# controller_v0.net
KiCad netlist of a schematic drawn in EAGLE
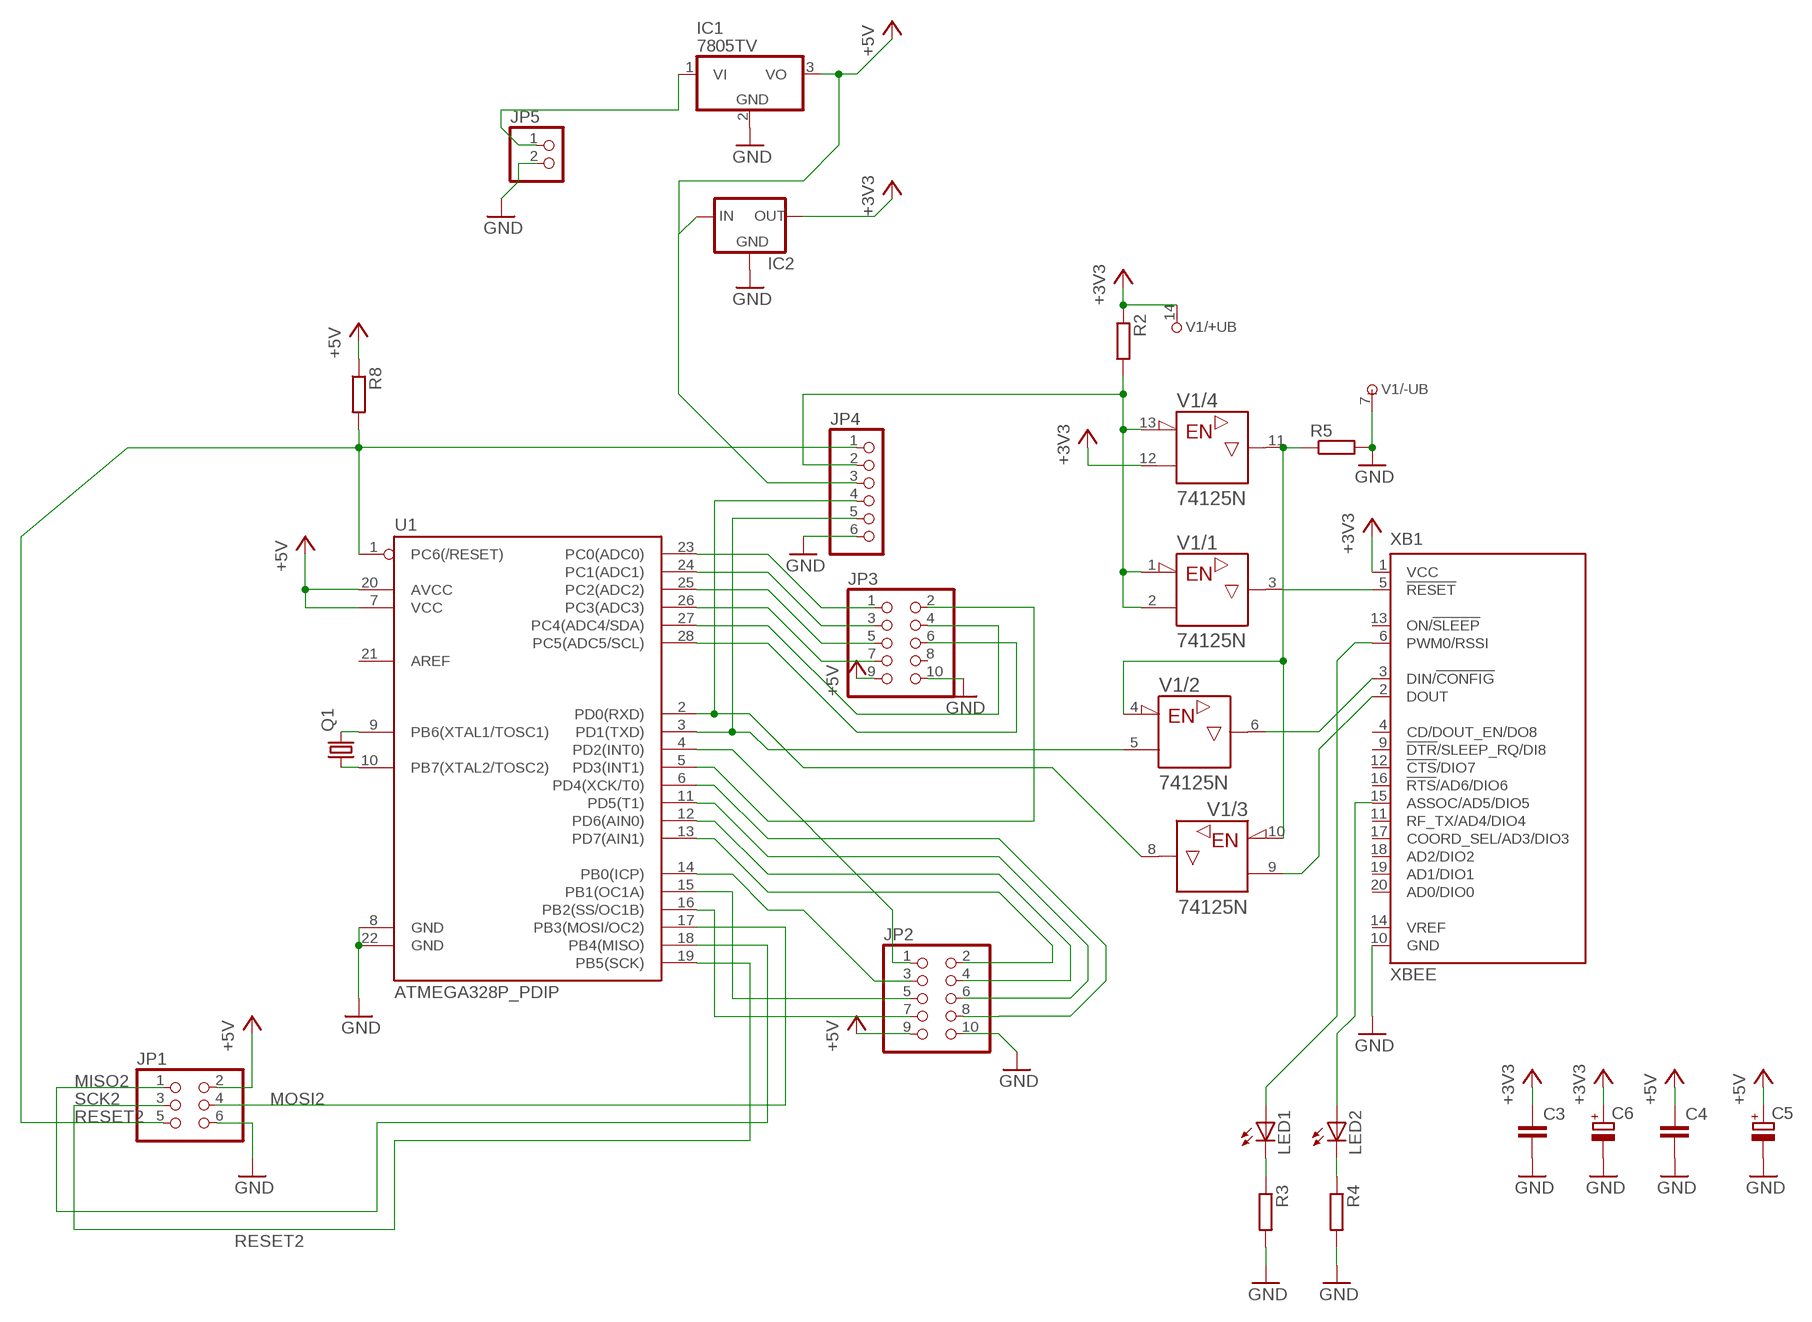
[diagram p0: schematic, sheet 1]

(export (version "E")
  (design (tool "Eeschema 10.0.6"))
  (components
    (comp (ref "C3")
      (value "C-EU025-025X050")
      (footprint "eagle-import:C025-025X050")
      (libsource (lib "eagle-import") (part "C-EU025-025X050"))
    )
    (comp (ref "C4")
      (value "C-EU025-025X050")
      (footprint "eagle-import:C025-025X050")
      (libsource (lib "eagle-import") (part "C-EU025-025X050"))
    )
    (comp (ref "C5")
      (value "CPOL-EUE2.5-6")
      (footprint "eagle-import:E2,5-6")
      (libsource (lib "eagle-import") (part "CPOL-EUE2.5-6"))
    )
    (comp (ref "C6")
      (value "CPOL-EUE2.5-6")
      (footprint "eagle-import:E2,5-6")
      (libsource (lib "eagle-import") (part "CPOL-EUE2.5-6"))
    )
    (comp (ref "IC1")
      (value "7805TV")
      (footprint "eagle-import:TO220V")
      (libsource (lib "eagle-import") (part "78TV05"))
    )
    (comp (ref "IC2")
      (value "78LXX")
      (footprint "eagle-import:78LXX")
      (libsource (lib "eagle-import") (part "78LXX"))
    )
    (comp (ref "JP1")
      (value "PINHD-2X3")
      (footprint "eagle-import:2X03")
      (libsource (lib "eagle-import") (part "PINHD-2X3"))
    )
    (comp (ref "JP2")
      (value "PINHD-2X5")
      (footprint "eagle-import:2X05")
      (libsource (lib "eagle-import") (part "PINHD-2X5"))
    )
    (comp (ref "JP3")
      (value "PINHD-2X5")
      (footprint "eagle-import:2X05")
      (libsource (lib "eagle-import") (part "PINHD-2X5"))
    )
    (comp (ref "JP4")
      (value "PINHD-1X6")
      (footprint "eagle-import:1X06")
      (libsource (lib "eagle-import") (part "PINHD-1X6"))
    )
    (comp (ref "JP5")
      (value "PINHD-1X2")
      (footprint "eagle-import:1X02")
      (libsource (lib "eagle-import") (part "PINHD-1X2"))
    )
    (comp (ref "LED1")
      (value "LED3MM")
      (footprint "eagle-import:LED3MM")
      (libsource (lib "eagle-import") (part "LED3MM"))
    )
    (comp (ref "LED2")
      (value "LED3MM")
      (footprint "eagle-import:LED3MM")
      (libsource (lib "eagle-import") (part "LED3MM"))
    )
    (comp (ref "Q1")
      (value "CRYSTALHC49S")
      (footprint "eagle-import:HC49_S")
      (libsource (lib "eagle-import") (part "CRYSTALHC49S"))
    )
    (comp (ref "R2")
      (value "R-EU_0204/7")
      (footprint "eagle-import:0204_7")
      (libsource (lib "eagle-import") (part "R-EU_0204/7"))
    )
    (comp (ref "R3")
      (value "R-EU_0204/7")
      (footprint "eagle-import:0204_7")
      (libsource (lib "eagle-import") (part "R-EU_0204/7"))
    )
    (comp (ref "R4")
      (value "R-EU_0204/7")
      (footprint "eagle-import:0204_7")
      (libsource (lib "eagle-import") (part "R-EU_0204/7"))
    )
    (comp (ref "R5")
      (value "R-EU_0204/7")
      (footprint "eagle-import:0204_7")
      (libsource (lib "eagle-import") (part "R-EU_0204/7"))
    )
    (comp (ref "R8")
      (value "R-EU_0204/7")
      (footprint "eagle-import:0204_7")
      (libsource (lib "eagle-import") (part "R-EU_0204/7"))
    )
    (comp (ref "U1")
      (value "ATMEGA328P_PDIP")
      (footprint "eagle-import:DIL28-3")
      (libsource (lib "eagle-import") (part "ATMEGA328P_PDIP"))
    )
    (comp (ref "V1")
      (value "74125N")
      (footprint "eagle-import:DIL14")
      (libsource (lib "eagle-import") (part "74125N"))
    )
    (comp (ref "XB1")
      (value "XBEE")
      (footprint "eagle-import:XBEE")
      (fields (field (name "MPN") "XBP24-Z7UIT-004"))
      (libsource (lib "eagle-import") (part "XBEE"))
    )
  )
  (nets
    (net (code "1") (name "+3V3") (class "Default")
      (node (ref "C3") (pin "1") (pinfunction "1_1") (pintype "passive"))
      (node (ref "C6") (pin "+") (pinfunction "+_+") (pintype "passive"))
      (node (ref "IC2") (pin "OUT") (pinfunction "OUT_OUT") (pintype "passive"))
      (node (ref "R2") (pin "1") (pinfunction "1_1") (pintype "passive"))
      (node (ref "V1") (pin "12") (pinfunction "A_12") (pintype "input"))
      (node (ref "V1") (pin "14") (pinfunction "+UB_14") (pintype "power_in"))
      (node (ref "XB1") (pin "1") (pinfunction "VCC_1") (pintype "power_in"))
    )
    (net (code "2") (name "+5V") (class "Default")
      (node (ref "C4") (pin "1") (pinfunction "1_1") (pintype "passive"))
      (node (ref "C5") (pin "+") (pinfunction "+_+") (pintype "passive"))
      (node (ref "IC1") (pin "3") (pinfunction "VO_3") (pintype "passive"))
      (node (ref "IC2") (pin "IN") (pinfunction "IN_IN") (pintype "input"))
      (node (ref "JP1") (pin "2") (pinfunction "2_2") (pintype "passive"))
      (node (ref "JP2") (pin "9") (pinfunction "9_9") (pintype "passive"))
      (node (ref "JP3") (pin "9") (pinfunction "9_9") (pintype "passive"))
      (node (ref "JP4") (pin "3") (pinfunction "3_3") (pintype "passive"))
      (node (ref "R8") (pin "1") (pinfunction "1_1") (pintype "passive"))
      (node (ref "U1") (pin "20") (pinfunction "AVCC_20") (pintype "bidirectional"))
      (node (ref "U1") (pin "7") (pinfunction "VCC_7") (pintype "bidirectional"))
    )
    (net (code "3") (name "/MISO2") (class "Default")
      (node (ref "JP1") (pin "1") (pinfunction "1_1") (pintype "passive"))
      (node (ref "U1") (pin "18") (pinfunction "PB4(MISO)_18") (pintype "bidirectional"))
    )
    (net (code "4") (name "/MOSI2") (class "Default")
      (node (ref "JP1") (pin "4") (pinfunction "4_4") (pintype "passive"))
      (node (ref "U1") (pin "17") (pinfunction "PB3(MOSI/OC2)_17") (pintype "bidirectional"))
    )
    (net (code "5") (name "/RESET2") (class "Default")
      (node (ref "JP1") (pin "5") (pinfunction "5_5") (pintype "passive"))
      (node (ref "JP4") (pin "1") (pinfunction "1_1") (pintype "passive"))
      (node (ref "R8") (pin "2") (pinfunction "2_2") (pintype "passive"))
      (node (ref "U1") (pin "1") (pinfunction "PC6(/RESET)_1") (pintype "bidirectional"))
    )
    (net (code "6") (name "/SCK2") (class "Default")
      (node (ref "JP1") (pin "3") (pinfunction "3_3") (pintype "passive"))
      (node (ref "U1") (pin "19") (pinfunction "PB5(SCK)_19") (pintype "bidirectional"))
    )
    (net (code "7") (name "GND") (class "Default")
      (node (ref "C3") (pin "2") (pinfunction "2_2") (pintype "passive"))
      (node (ref "C4") (pin "2") (pinfunction "2_2") (pintype "passive"))
      (node (ref "C5") (pin "-") (pinfunction "-_-") (pintype "passive"))
      (node (ref "C6") (pin "-") (pinfunction "-_-") (pintype "passive"))
      (node (ref "IC1") (pin "2") (pinfunction "GND_2") (pintype "passive"))
      (node (ref "IC2") (pin "GND") (pinfunction "GND_GND") (pintype "input"))
      (node (ref "JP1") (pin "6") (pinfunction "6_6") (pintype "passive"))
      (node (ref "JP2") (pin "10") (pinfunction "10_10") (pintype "passive"))
      (node (ref "JP3") (pin "10") (pinfunction "10_10") (pintype "passive"))
      (node (ref "JP4") (pin "6") (pinfunction "6_6") (pintype "passive"))
      (node (ref "JP5") (pin "2") (pinfunction "2_2") (pintype "passive"))
      (node (ref "R3") (pin "2") (pinfunction "2_2") (pintype "passive"))
      (node (ref "R4") (pin "2") (pinfunction "2_2") (pintype "passive"))
      (node (ref "R5") (pin "2") (pinfunction "2_2") (pintype "passive"))
      (node (ref "U1") (pin "22") (pinfunction "GND_22") (pintype "bidirectional"))
      (node (ref "U1") (pin "8") (pinfunction "GND_8") (pintype "bidirectional"))
      (node (ref "V1") (pin "7") (pinfunction "-UB_7") (pintype "power_in"))
      (node (ref "XB1") (pin "10") (pinfunction "GND_10") (pintype "power_in"))
    )
    (net (code "8") (name "Net-(IC1-VI)") (class "Default")
      (node (ref "IC1") (pin "1") (pinfunction "VI_1") (pintype "input"))
      (node (ref "JP5") (pin "1") (pinfunction "1_1") (pintype "passive"))
    )
    (net (code "9") (name "Net-(LED1-C)") (class "Default")
      (node (ref "LED1") (pin "K") (pinfunction "C_K") (pintype "passive"))
      (node (ref "R3") (pin "1") (pinfunction "1_1") (pintype "passive"))
    )
    (net (code "10") (name "Net-(LED2-C)") (class "Default")
      (node (ref "LED2") (pin "K") (pinfunction "C_K") (pintype "passive"))
      (node (ref "R4") (pin "1") (pinfunction "1_1") (pintype "passive"))
    )
    (net (code "11") (name "Net-(U1-PB0(ICP))") (class "Default")
      (node (ref "JP2") (pin "3") (pinfunction "3_3") (pintype "passive"))
      (node (ref "U1") (pin "14") (pinfunction "PB0(ICP)_14") (pintype "bidirectional"))
    )
    (net (code "12") (name "Net-(U1-PB1(OC1A))") (class "Default")
      (node (ref "JP2") (pin "5") (pinfunction "5_5") (pintype "passive"))
      (node (ref "U1") (pin "15") (pinfunction "PB1(OC1A)_15") (pintype "bidirectional"))
    )
    (net (code "13") (name "Net-(U1-PB2(SS{slash}OC1B))") (class "Default")
      (node (ref "JP2") (pin "7") (pinfunction "7_7") (pintype "passive"))
      (node (ref "U1") (pin "16") (pinfunction "PB2(SS/OC1B)_16") (pintype "bidirectional"))
    )
    (net (code "14") (name "Net-(U1-PB6(XTAL1{slash}TOSC1))") (class "Default")
      (node (ref "Q1") (pin "2") (pinfunction "2_2") (pintype "passive"))
      (node (ref "U1") (pin "9") (pinfunction "PB6(XTAL1/TOSC1)_9") (pintype "bidirectional"))
    )
    (net (code "15") (name "Net-(U1-PB7(XTAL2{slash}TOSC2))") (class "Default")
      (node (ref "Q1") (pin "1") (pinfunction "1_1") (pintype "passive"))
      (node (ref "U1") (pin "10") (pinfunction "PB7(XTAL2/TOSC2)_10") (pintype "bidirectional"))
    )
    (net (code "16") (name "Net-(U1-PC0(ADC0))") (class "Default")
      (node (ref "JP3") (pin "1") (pinfunction "1_1") (pintype "passive"))
      (node (ref "U1") (pin "23") (pinfunction "PC0(ADC0)_23") (pintype "bidirectional"))
    )
    (net (code "17") (name "Net-(U1-PC1(ADC1))") (class "Default")
      (node (ref "JP3") (pin "3") (pinfunction "3_3") (pintype "passive"))
      (node (ref "U1") (pin "24") (pinfunction "PC1(ADC1)_24") (pintype "bidirectional"))
    )
    (net (code "18") (name "Net-(U1-PC2(ADC2))") (class "Default")
      (node (ref "JP3") (pin "5") (pinfunction "5_5") (pintype "passive"))
      (node (ref "U1") (pin "25") (pinfunction "PC2(ADC2)_25") (pintype "bidirectional"))
    )
    (net (code "19") (name "Net-(U1-PC3(ADC3))") (class "Default")
      (node (ref "JP3") (pin "7") (pinfunction "7_7") (pintype "passive"))
      (node (ref "U1") (pin "26") (pinfunction "PC3(ADC3)_26") (pintype "bidirectional"))
    )
    (net (code "20") (name "Net-(U1-PC4(ADC4{slash}SDA))") (class "Default")
      (node (ref "JP3") (pin "4") (pinfunction "4_4") (pintype "passive"))
      (node (ref "U1") (pin "27") (pinfunction "PC4(ADC4/SDA)_27") (pintype "bidirectional"))
    )
    (net (code "21") (name "Net-(U1-PC5(ADC5{slash}SCL))") (class "Default")
      (node (ref "JP3") (pin "6") (pinfunction "6_6") (pintype "passive"))
      (node (ref "U1") (pin "28") (pinfunction "PC5(ADC5/SCL)_28") (pintype "bidirectional"))
    )
    (net (code "22") (name "Net-(U1-PD0(RXD))") (class "Default")
      (node (ref "JP4") (pin "4") (pinfunction "4_4") (pintype "passive"))
      (node (ref "U1") (pin "2") (pinfunction "PD0(RXD)_2") (pintype "bidirectional"))
      (node (ref "V1") (pin "8") (pinfunction "Y_8") (pintype "tri_state"))
    )
    (net (code "23") (name "Net-(U1-PD1(TXD))") (class "Default")
      (node (ref "JP4") (pin "5") (pinfunction "5_5") (pintype "passive"))
      (node (ref "U1") (pin "3") (pinfunction "PD1(TXD)_3") (pintype "bidirectional"))
      (node (ref "V1") (pin "5") (pinfunction "A_5") (pintype "input"))
    )
    (net (code "24") (name "Net-(U1-PD2(INT0))") (class "Default")
      (node (ref "JP2") (pin "1") (pinfunction "1_1") (pintype "passive"))
      (node (ref "U1") (pin "4") (pinfunction "PD2(INT0)_4") (pintype "bidirectional"))
    )
    (net (code "25") (name "Net-(U1-PD3(INT1))") (class "Default")
      (node (ref "JP3") (pin "2") (pinfunction "2_2") (pintype "passive"))
      (node (ref "U1") (pin "5") (pinfunction "PD3(INT1)_5") (pintype "bidirectional"))
    )
    (net (code "26") (name "Net-(U1-PD4(XCK{slash}T0))") (class "Default")
      (node (ref "JP2") (pin "8") (pinfunction "8_8") (pintype "passive"))
      (node (ref "U1") (pin "6") (pinfunction "PD4(XCK/T0)_6") (pintype "bidirectional"))
    )
    (net (code "27") (name "Net-(U1-PD5(T1))") (class "Default")
      (node (ref "JP2") (pin "6") (pinfunction "6_6") (pintype "passive"))
      (node (ref "U1") (pin "11") (pinfunction "PD5(T1)_11") (pintype "bidirectional"))
    )
    (net (code "28") (name "Net-(U1-PD6(AIN0))") (class "Default")
      (node (ref "JP2") (pin "4") (pinfunction "4_4") (pintype "passive"))
      (node (ref "U1") (pin "12") (pinfunction "PD6(AIN0)_12") (pintype "bidirectional"))
    )
    (net (code "29") (name "Net-(U1-PD7(AIN1))") (class "Default")
      (node (ref "JP2") (pin "2") (pinfunction "2_2") (pintype "passive"))
      (node (ref "U1") (pin "13") (pinfunction "PD7(AIN1)_13") (pintype "bidirectional"))
    )
    (net (code "30") (name "Net-(V1C-A)") (class "Default")
      (node (ref "JP4") (pin "2") (pinfunction "2_2") (pintype "passive"))
      (node (ref "R2") (pin "2") (pinfunction "2_2") (pintype "passive"))
      (node (ref "V1") (pin "1") (pinfunction "~{G}_1") (pintype "input"))
      (node (ref "V1") (pin "13") (pinfunction "~{G}_13") (pintype "input"))
      (node (ref "V1") (pin "2") (pinfunction "A_2") (pintype "input"))
    )
    (net (code "31") (name "Net-(V1C-Y)") (class "Default")
      (node (ref "V1") (pin "3") (pinfunction "Y_3") (pintype "tri_state"))
      (node (ref "XB1") (pin "5") (pinfunction "~{RESET}_5") (pintype "input"))
    )
    (net (code "32") (name "Net-(V1D-Y)") (class "Default")
      (node (ref "V1") (pin "6") (pinfunction "Y_6") (pintype "tri_state"))
      (node (ref "XB1") (pin "3") (pinfunction "DIN/~{CONFIG}_3") (pintype "input"))
    )
    (net (code "33") (name "Net-(V1D-~{G})") (class "Default")
      (node (ref "R5") (pin "1") (pinfunction "1_1") (pintype "passive"))
      (node (ref "V1") (pin "10") (pinfunction "~{G}_10") (pintype "input"))
      (node (ref "V1") (pin "11") (pinfunction "Y_11") (pintype "tri_state"))
      (node (ref "V1") (pin "4") (pinfunction "~{G}_4") (pintype "input"))
    )
    (net (code "34") (name "Net-(V1E-A)") (class "Default")
      (node (ref "V1") (pin "9") (pinfunction "A_9") (pintype "input"))
      (node (ref "XB1") (pin "2") (pinfunction "DOUT_2") (pintype "output"))
    )
    (net (code "35") (name "Net-(XB1-ASSOC{slash}AD5{slash}DIO5)") (class "Default")
      (node (ref "LED2") (pin "A") (pinfunction "A_A") (pintype "passive"))
      (node (ref "XB1") (pin "15") (pinfunction "ASSOC/AD5/DIO5_15") (pintype "bidirectional"))
    )
    (net (code "36") (name "Net-(XB1-PWM0{slash}RSSI)") (class "Default")
      (node (ref "LED1") (pin "A") (pinfunction "A_A") (pintype "passive"))
      (node (ref "XB1") (pin "6") (pinfunction "PWM0/RSSI_6") (pintype "output"))
    )
    (net (code "37") (name "unconnected-(JP3-Pad8)") (class "Default")
      (node (ref "JP3") (pin "8") (pinfunction "8_8") (pintype "passive"))
    )
    (net (code "38") (name "unconnected-(U1-AREF-Pad21)") (class "Default")
      (node (ref "U1") (pin "21") (pinfunction "AREF_21") (pintype "bidirectional"))
    )
    (net (code "39") (name "unconnected-(XB1-AD0{slash}DIO0-Pad20)") (class "Default")
      (node (ref "XB1") (pin "20") (pinfunction "AD0/DIO0_20") (pintype "bidirectional"))
    )
    (net (code "40") (name "unconnected-(XB1-AD1{slash}DIO1-Pad19)") (class "Default")
      (node (ref "XB1") (pin "19") (pinfunction "AD1/DIO1_19") (pintype "bidirectional"))
    )
    (net (code "41") (name "unconnected-(XB1-AD2{slash}DIO2-Pad18)") (class "Default")
      (node (ref "XB1") (pin "18") (pinfunction "AD2/DIO2_18") (pintype "bidirectional"))
    )
    (net (code "42") (name "unconnected-(XB1-CD{slash}DOUT_EN{slash}DO8-Pad4)") (class "Default")
      (node (ref "XB1") (pin "4") (pinfunction "CD/DOUT_EN/DO8_4") (pintype "output"))
    )
    (net (code "43") (name "unconnected-(XB1-COORD_SEL{slash}AD3{slash}DIO3-Pad17)") (class "Default")
      (node (ref "XB1") (pin "17") (pinfunction "COORD_SEL/AD3/DIO3_17") (pintype "bidirectional"))
    )
    (net (code "44") (name "unconnected-(XB1-ON{slash}~{SLEEP}-Pad13)") (class "Default")
      (node (ref "XB1") (pin "13") (pinfunction "ON/~{SLEEP}_13") (pintype "output"))
    )
    (net (code "45") (name "unconnected-(XB1-RF_TX{slash}AD4{slash}DIO4-Pad11)") (class "Default")
      (node (ref "XB1") (pin "11") (pinfunction "RF_TX/AD4/DIO4_11") (pintype "bidirectional"))
    )
    (net (code "46") (name "unconnected-(XB1-VREF-Pad14)") (class "Default")
      (node (ref "XB1") (pin "14") (pinfunction "VREF_14") (pintype "input"))
    )
    (net (code "47") (name "unconnected-(XB1-~{CTS}{slash}DIO7-Pad12)") (class "Default")
      (node (ref "XB1") (pin "12") (pinfunction "~{CTS}/DIO7_12") (pintype "bidirectional"))
    )
    (net (code "48") (name "unconnected-(XB1-~{DTR}{slash}SLEEP_RQ{slash}DI8-Pad9)") (class "Default")
      (node (ref "XB1") (pin "9") (pinfunction "~{DTR}/SLEEP_RQ/DI8_9") (pintype "bidirectional"))
    )
    (net (code "49") (name "unconnected-(XB1-~{RTS}{slash}AD6{slash}DIO6-Pad16)") (class "Default")
      (node (ref "XB1") (pin "16") (pinfunction "~{RTS}/AD6/DIO6_16") (pintype "bidirectional"))
    )
  )
)
